# exercise2.net
KiCad netlist of a schematic drawn in Altium Designer
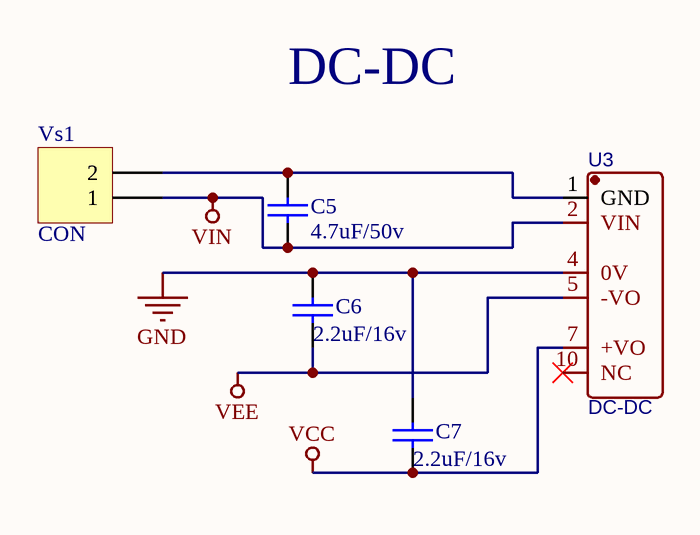
[diagram p0: exercise2.SchDoc]

(export (version "E")
  (design (tool "Eeschema 10.0.6"))
  (components
    (comp (ref "C5")
      (value "4.7uF/50v")
      (footprint "RAD-0.3")
      (description "Capacitor")
      (fields (field (name "Comment") "Cap") (field (name "PUBLISHER") "Altium Limited"))
      (libsource (lib "Miscellaneous Devices") (part "Cap"))
    )
    (comp (ref "C6")
      (value "2.2uF/16v")
      (footprint "RAD-0.3")
      (description "Capacitor")
      (fields (field (name "Comment") "Cap") (field (name "PUBLISHER") "Altium Limited"))
      (libsource (lib "Miscellaneous Devices") (part "Cap"))
    )
    (comp (ref "C7")
      (value "2.2uF/16v")
      (footprint "RAD-0.3")
      (description "Capacitor")
      (fields (field (name "Comment") "Cap") (field (name "PUBLISHER") "Altium Limited"))
      (libsource (lib "Miscellaneous Devices") (part "Cap"))
    )
    (comp (ref "U3")
      (value "DC-DC")
      (footprint "DC-DC")
      (fields
        (field (name "BOM_MANUFACTURER PART") "A0515XT-1WR2")
        (field (name "BOM_SUPPLIER PART") "C58972")
      )
      (libsource (lib "dzsx") (part "DC-DC"))
    )
    (comp (ref "Vs1")
      (value "CON")
      (footprint "HDR1X2")
      (description "Header, 2-Pin")
      (fields (field (name "PUBLISHER") "Altium Limited"))
      (libsource (lib "Miscellaneous Connectors") (part "Header 2"))
    )
  )
  (nets
    (net (code "1") (name "GND") (class "Default")
      (node (ref "C6") (pin "2") (pinfunction "2_2") (pintype "passive"))
      (node (ref "C7") (pin "2") (pinfunction "2_2") (pintype "passive"))
      (node (ref "U3") (pin "4") (pinfunction "0V_4") (pintype "passive"))
    )
    (net (code "2") (name "Net-(U3-GND)") (class "Default")
      (node (ref "C5") (pin "2") (pinfunction "2_2") (pintype "passive"))
      (node (ref "U3") (pin "1") (pinfunction "GND_1") (pintype "passive"))
      (node (ref "Vs1") (pin "2") (pinfunction "2_2") (pintype "passive"))
    )
    (net (code "3") (name "VCC") (class "Default")
      (node (ref "C7") (pin "1") (pinfunction "1_1") (pintype "passive"))
      (node (ref "U3") (pin "7") (pinfunction "+VO_7") (pintype "passive"))
    )
    (net (code "4") (name "VEE") (class "Default")
      (node (ref "C6") (pin "1") (pinfunction "1_1") (pintype "passive"))
      (node (ref "U3") (pin "5") (pinfunction "-VO_5") (pintype "passive"))
    )
    (net (code "5") (name "VIN") (class "Default")
      (node (ref "C5") (pin "1") (pinfunction "1_1") (pintype "passive"))
      (node (ref "U3") (pin "2") (pinfunction "VIN_2") (pintype "passive"))
      (node (ref "Vs1") (pin "1") (pinfunction "1_1") (pintype "passive"))
    )
    (net (code "6") (name "unconnected-(U3-NC-Pad10)") (class "Default")
      (node (ref "U3") (pin "10") (pinfunction "NC_10") (pintype "passive+no_connect"))
    )
  )
)
